# as14120_x31_fpga_power_conf.net
KiCad netlist of a schematic drawn in Altium Designer
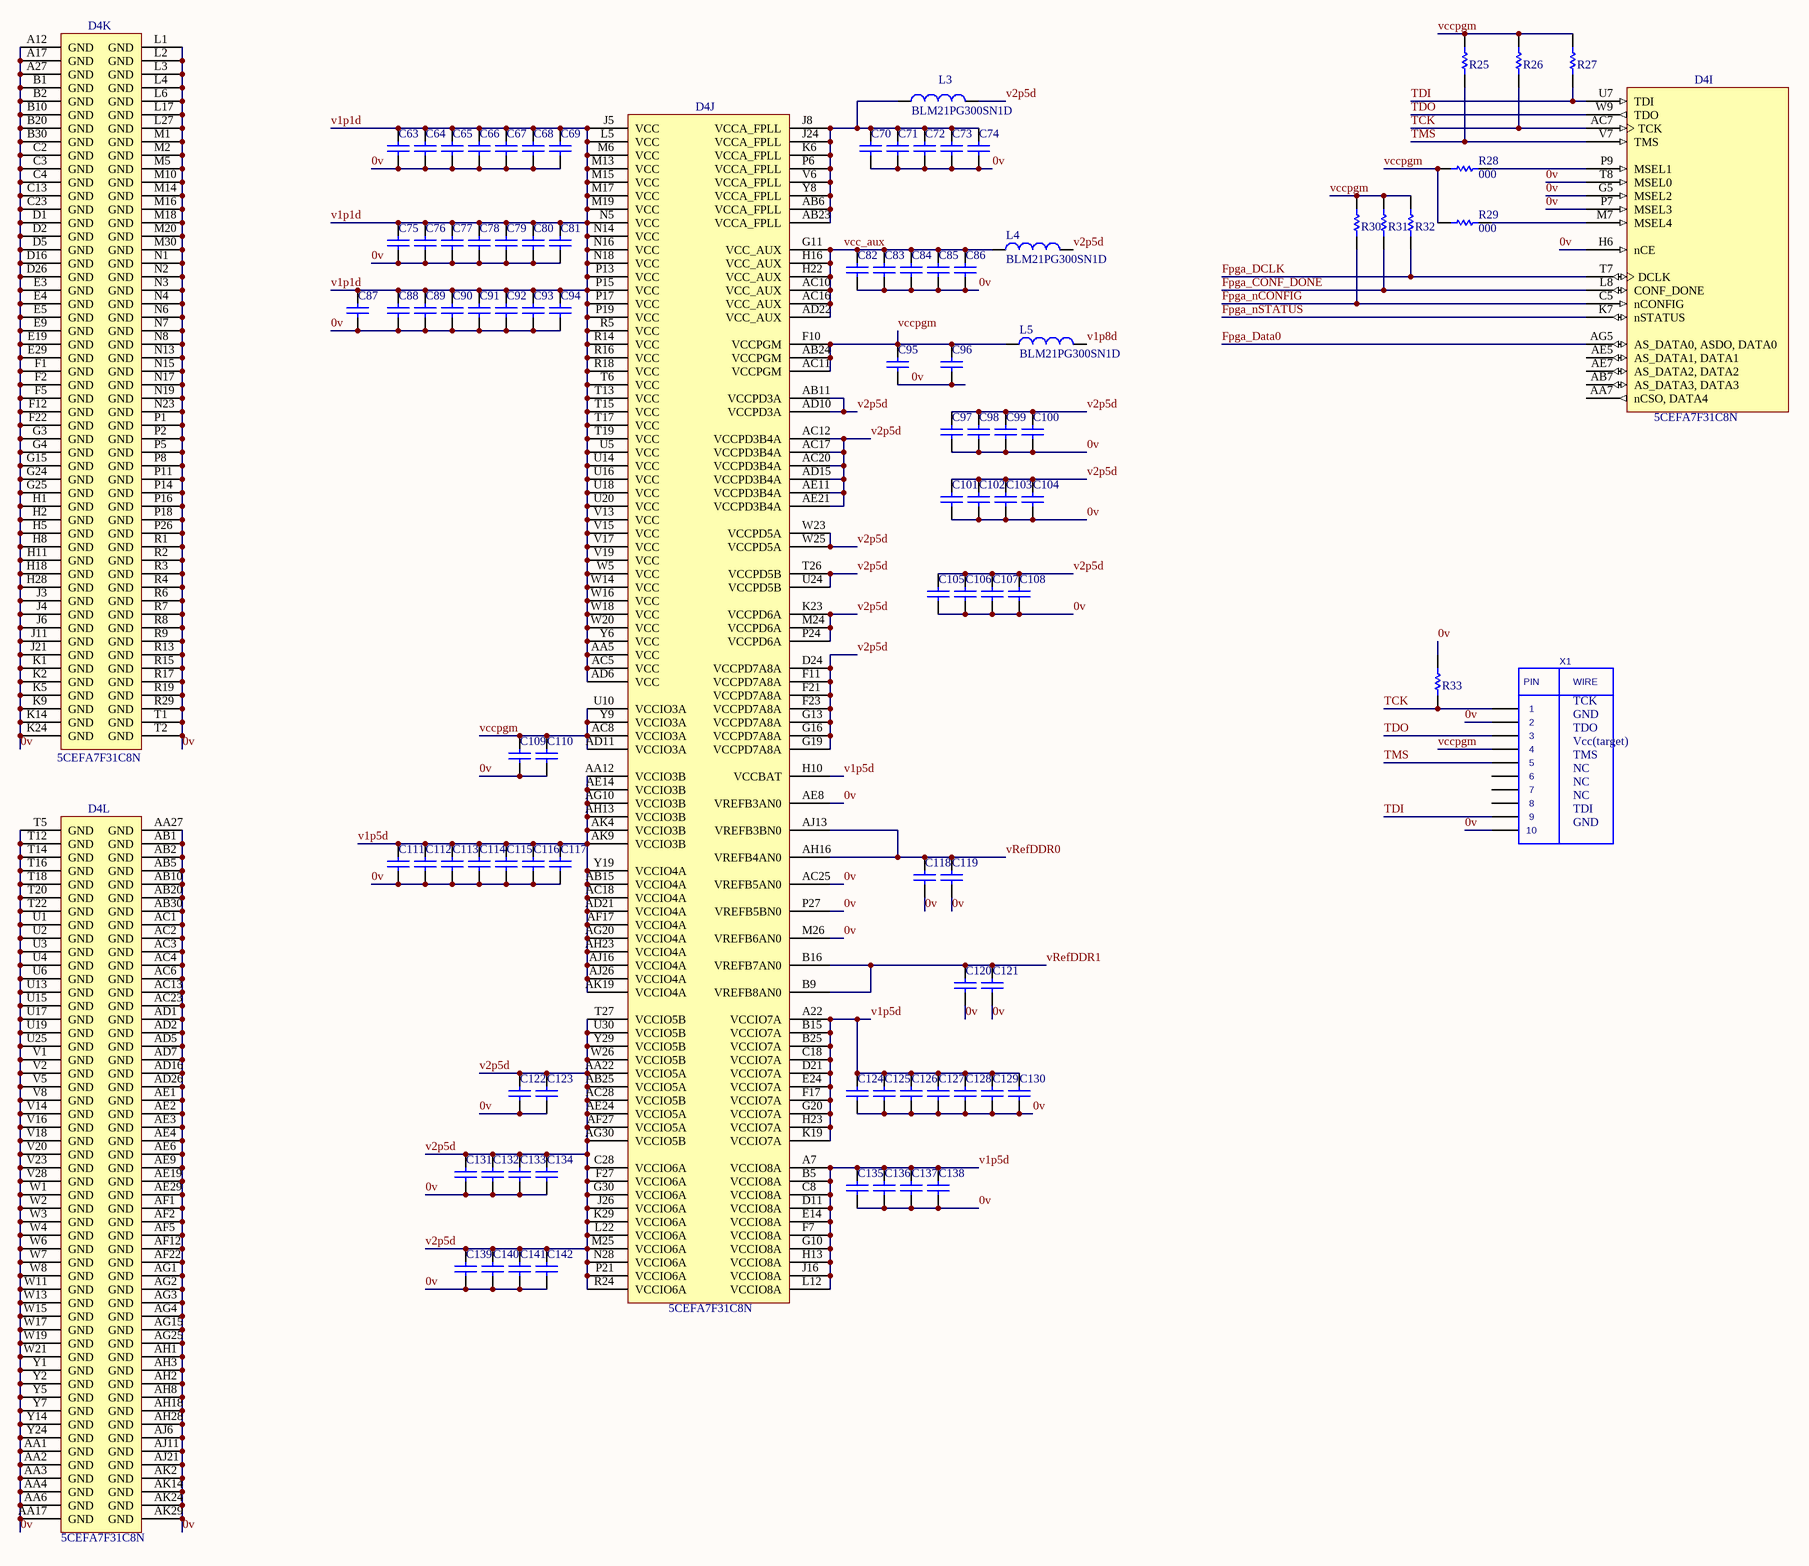
[diagram p0: as14120_x31_fpga_power_conf.SchDoc]

(export (version "E")
  (design (tool "Eeschema 10.0.6"))
  (components
    (comp (ref "C63")
      (value "CAP 1uF 10V 0402(1005)")
      (footprint "CAPC0402(1005)60_M")
      (description "CAP 1uF 10V ±20% 0402 (1005 Metric) Thickness 0.6mm SMD")
      (fields (field (name "TOLERANCE") "±20%"))
      (libsource (lib "as14120") (part "CAP_0402"))
    )
    (comp (ref "C64")
      (value "CAP 1uF 10V 0402(1005)")
      (footprint "CAPC0402(1005)60_M")
      (description "CAP 1uF 10V ±20% 0402 (1005 Metric) Thickness 0.6mm SMD")
      (fields (field (name "TOLERANCE") "±20%"))
      (libsource (lib "as14120") (part "CAP_0402"))
    )
    (comp (ref "C65")
      (value "CAP 1uF 10V 0402(1005)")
      (footprint "CAPC0402(1005)60_M")
      (description "CAP 1uF 10V ±20% 0402 (1005 Metric) Thickness 0.6mm SMD")
      (fields (field (name "TOLERANCE") "±20%"))
      (libsource (lib "as14120") (part "CAP_0402"))
    )
    (comp (ref "C66")
      (value "CAP 1uF 10V 0402(1005)")
      (footprint "CAPC0402(1005)60_M")
      (description "CAP 1uF 10V ±20% 0402 (1005 Metric) Thickness 0.6mm SMD")
      (fields (field (name "TOLERANCE") "±20%"))
      (libsource (lib "as14120") (part "CAP_0402"))
    )
    (comp (ref "C67")
      (value "CAP 1uF 10V 0402(1005)")
      (footprint "CAPC0402(1005)60_M")
      (description "CAP 1uF 10V ±20% 0402 (1005 Metric) Thickness 0.6mm SMD")
      (fields (field (name "TOLERANCE") "±20%"))
      (libsource (lib "as14120") (part "CAP_0402"))
    )
    (comp (ref "C68")
      (value "CAP 1uF 10V 0402(1005)")
      (footprint "CAPC0402(1005)60_M")
      (description "CAP 1uF 10V ±20% 0402 (1005 Metric) Thickness 0.6mm SMD")
      (fields (field (name "TOLERANCE") "±20%"))
      (libsource (lib "as14120") (part "CAP_0402"))
    )
    (comp (ref "C69")
      (value "CAP 1uF 10V 0402(1005)")
      (footprint "CAPC0402(1005)60_M")
      (description "CAP 1uF 10V ±20% 0402 (1005 Metric) Thickness 0.6mm SMD")
      (fields (field (name "TOLERANCE") "±20%"))
      (libsource (lib "as14120") (part "CAP_0402"))
    )
    (comp (ref "C70")
      (value "CAP 1uF 10V 0402(1005)")
      (footprint "CAPC0402(1005)60_M")
      (description "CAP 1uF 10V ±20% 0402 (1005 Metric) Thickness 0.6mm SMD")
      (fields (field (name "TOLERANCE") "±20%"))
      (libsource (lib "as14120") (part "CAP_0402"))
    )
    (comp (ref "C71")
      (value "CAP 1uF 10V 0402(1005)")
      (footprint "CAPC0402(1005)60_M")
      (description "CAP 1uF 10V ±20% 0402 (1005 Metric) Thickness 0.6mm SMD")
      (fields (field (name "TOLERANCE") "±20%"))
      (libsource (lib "as14120") (part "CAP_0402"))
    )
    (comp (ref "C72")
      (value "CAP 1uF 10V 0402(1005)")
      (footprint "CAPC0402(1005)60_M")
      (description "CAP 1uF 10V ±20% 0402 (1005 Metric) Thickness 0.6mm SMD")
      (fields (field (name "TOLERANCE") "±20%"))
      (libsource (lib "as14120") (part "CAP_0402"))
    )
    (comp (ref "C73")
      (value "CAP 1uF 10V 0402(1005)")
      (footprint "CAPC0402(1005)60_M")
      (description "CAP 1uF 10V ±20% 0402 (1005 Metric) Thickness 0.6mm SMD")
      (fields (field (name "TOLERANCE") "±20%"))
      (libsource (lib "as14120") (part "CAP_0402"))
    )
    (comp (ref "C74")
      (value "CAP 1uF 10V 0402(1005)")
      (footprint "CAPC0402(1005)60_M")
      (description "CAP 1uF 10V ±20% 0402 (1005 Metric) Thickness 0.6mm SMD")
      (fields (field (name "TOLERANCE") "±20%"))
      (libsource (lib "as14120") (part "CAP_0402"))
    )
    (comp (ref "C75")
      (value "CAP 1uF 10V 0402(1005)")
      (footprint "CAPC0402(1005)60_M")
      (description "CAP 1uF 10V ±20% 0402 (1005 Metric) Thickness 0.6mm SMD")
      (fields (field (name "TOLERANCE") "±20%"))
      (libsource (lib "as14120") (part "CAP_0402"))
    )
    (comp (ref "C76")
      (value "CAP 1uF 10V 0402(1005)")
      (footprint "CAPC0402(1005)60_M")
      (description "CAP 1uF 10V ±20% 0402 (1005 Metric) Thickness 0.6mm SMD")
      (fields (field (name "TOLERANCE") "±20%"))
      (libsource (lib "as14120") (part "CAP_0402"))
    )
    (comp (ref "C77")
      (value "CAP 1uF 10V 0402(1005)")
      (footprint "CAPC0402(1005)60_M")
      (description "CAP 1uF 10V ±20% 0402 (1005 Metric) Thickness 0.6mm SMD")
      (fields (field (name "TOLERANCE") "±20%"))
      (libsource (lib "as14120") (part "CAP_0402"))
    )
    (comp (ref "C78")
      (value "CAP 1uF 10V 0402(1005)")
      (footprint "CAPC0402(1005)60_M")
      (description "CAP 1uF 10V ±20% 0402 (1005 Metric) Thickness 0.6mm SMD")
      (fields (field (name "TOLERANCE") "±20%"))
      (libsource (lib "as14120") (part "CAP_0402"))
    )
    (comp (ref "C79")
      (value "CAP 1uF 10V 0402(1005)")
      (footprint "CAPC0402(1005)60_M")
      (description "CAP 1uF 10V ±20% 0402 (1005 Metric) Thickness 0.6mm SMD")
      (fields (field (name "TOLERANCE") "±20%"))
      (libsource (lib "as14120") (part "CAP_0402"))
    )
    (comp (ref "C80")
      (value "CAP 1uF 10V 0402(1005)")
      (footprint "CAPC0402(1005)60_M")
      (description "CAP 1uF 10V ±20% 0402 (1005 Metric) Thickness 0.6mm SMD")
      (fields (field (name "TOLERANCE") "±20%"))
      (libsource (lib "as14120") (part "CAP_0402"))
    )
    (comp (ref "C81")
      (value "CAP 1uF 10V 0402(1005)")
      (footprint "CAPC0402(1005)60_M")
      (description "CAP 1uF 10V ±20% 0402 (1005 Metric) Thickness 0.6mm SMD")
      (fields (field (name "TOLERANCE") "±20%"))
      (libsource (lib "as14120") (part "CAP_0402"))
    )
    (comp (ref "C82")
      (value "CAP 1uF 10V 0402(1005)")
      (footprint "CAPC0402(1005)60_M")
      (description "CAP 1uF 10V ±20% 0402 (1005 Metric) Thickness 0.6mm SMD")
      (fields (field (name "TOLERANCE") "±20%"))
      (libsource (lib "as14120") (part "CAP_0402"))
    )
    (comp (ref "C83")
      (value "CAP 1uF 10V 0402(1005)")
      (footprint "CAPC0402(1005)60_M")
      (description "CAP 1uF 10V ±20% 0402 (1005 Metric) Thickness 0.6mm SMD")
      (fields (field (name "TOLERANCE") "±20%"))
      (libsource (lib "as14120") (part "CAP_0402"))
    )
    (comp (ref "C84")
      (value "CAP 1uF 10V 0402(1005)")
      (footprint "CAPC0402(1005)60_M")
      (description "CAP 1uF 10V ±20% 0402 (1005 Metric) Thickness 0.6mm SMD")
      (fields (field (name "TOLERANCE") "±20%"))
      (libsource (lib "as14120") (part "CAP_0402"))
    )
    (comp (ref "C85")
      (value "CAP 1uF 10V 0402(1005)")
      (footprint "CAPC0402(1005)60_M")
      (description "CAP 1uF 10V ±20% 0402 (1005 Metric) Thickness 0.6mm SMD")
      (fields (field (name "TOLERANCE") "±20%"))
      (libsource (lib "as14120") (part "CAP_0402"))
    )
    (comp (ref "C86")
      (value "CAP 1uF 10V 0402(1005)")
      (footprint "CAPC0402(1005)60_M")
      (description "CAP 1uF 10V ±20% 0402 (1005 Metric) Thickness 0.6mm SMD")
      (fields (field (name "TOLERANCE") "±20%"))
      (libsource (lib "as14120") (part "CAP_0402"))
    )
    (comp (ref "C87")
      (value "CAP 1uF 10V 0402(1005)")
      (footprint "CAPC0402(1005)60_M")
      (description "CAP 1uF 10V ±20% 0402 (1005 Metric) Thickness 0.6mm SMD")
      (fields (field (name "TOLERANCE") "±20%"))
      (libsource (lib "as14120") (part "CAP_0402"))
    )
    (comp (ref "C88")
      (value "CAP 1uF 10V 0402(1005)")
      (footprint "CAPC0402(1005)60_M")
      (description "CAP 1uF 10V ±20% 0402 (1005 Metric) Thickness 0.6mm SMD")
      (fields (field (name "TOLERANCE") "±20%"))
      (libsource (lib "as14120") (part "CAP_0402"))
    )
    (comp (ref "C89")
      (value "CAP 1uF 10V 0402(1005)")
      (footprint "CAPC0402(1005)60_M")
      (description "CAP 1uF 10V ±20% 0402 (1005 Metric) Thickness 0.6mm SMD")
      (fields (field (name "TOLERANCE") "±20%"))
      (libsource (lib "as14120") (part "CAP_0402"))
    )
    (comp (ref "C90")
      (value "CAP 1uF 10V 0402(1005)")
      (footprint "CAPC0402(1005)60_M")
      (description "CAP 1uF 10V ±20% 0402 (1005 Metric) Thickness 0.6mm SMD")
      (fields (field (name "TOLERANCE") "±20%"))
      (libsource (lib "as14120") (part "CAP_0402"))
    )
    (comp (ref "C91")
      (value "CAP 1uF 10V 0402(1005)")
      (footprint "CAPC0402(1005)60_M")
      (description "CAP 1uF 10V ±20% 0402 (1005 Metric) Thickness 0.6mm SMD")
      (fields (field (name "TOLERANCE") "±20%"))
      (libsource (lib "as14120") (part "CAP_0402"))
    )
    (comp (ref "C92")
      (value "CAP 1uF 10V 0402(1005)")
      (footprint "CAPC0402(1005)60_M")
      (description "CAP 1uF 10V ±20% 0402 (1005 Metric) Thickness 0.6mm SMD")
      (fields (field (name "TOLERANCE") "±20%"))
      (libsource (lib "as14120") (part "CAP_0402"))
    )
    (comp (ref "C93")
      (value "CAP 1uF 10V 0402(1005)")
      (footprint "CAPC0402(1005)60_M")
      (description "CAP 1uF 10V ±20% 0402 (1005 Metric) Thickness 0.6mm SMD")
      (fields (field (name "TOLERANCE") "±20%"))
      (libsource (lib "as14120") (part "CAP_0402"))
    )
    (comp (ref "C94")
      (value "CAP 1uF 10V 0402(1005)")
      (footprint "CAPC0402(1005)60_M")
      (description "CAP 1uF 10V ±20% 0402 (1005 Metric) Thickness 0.6mm SMD")
      (fields (field (name "TOLERANCE") "±20%"))
      (libsource (lib "as14120") (part "CAP_0402"))
    )
    (comp (ref "C95")
      (value "CAP 1uF 10V 0402(1005)")
      (footprint "CAPC0402(1005)60_M")
      (description "CAP 1uF 10V ±20% 0402 (1005 Metric) Thickness 0.6mm SMD")
      (fields (field (name "TOLERANCE") "±20%"))
      (libsource (lib "as14120") (part "CAP_0402"))
    )
    (comp (ref "C96")
      (value "CAP 1uF 10V 0402(1005)")
      (footprint "CAPC0402(1005)60_M")
      (description "CAP 1uF 10V ±20% 0402 (1005 Metric) Thickness 0.6mm SMD")
      (fields (field (name "TOLERANCE") "±20%"))
      (libsource (lib "as14120") (part "CAP_0402"))
    )
    (comp (ref "C97")
      (value "CAP 1uF 10V 0402(1005)")
      (footprint "CAPC0402(1005)60_M")
      (description "CAP 1uF 10V ±20% 0402 (1005 Metric) Thickness 0.6mm SMD")
      (fields (field (name "TOLERANCE") "±20%"))
      (libsource (lib "as14120") (part "CAP_0402"))
    )
    (comp (ref "C98")
      (value "CAP 1uF 10V 0402(1005)")
      (footprint "CAPC0402(1005)60_M")
      (description "CAP 1uF 10V ±20% 0402 (1005 Metric) Thickness 0.6mm SMD")
      (fields (field (name "TOLERANCE") "±20%"))
      (libsource (lib "as14120") (part "CAP_0402"))
    )
    (comp (ref "C99")
      (value "CAP 1uF 10V 0402(1005)")
      (footprint "CAPC0402(1005)60_M")
      (description "CAP 1uF 10V ±20% 0402 (1005 Metric) Thickness 0.6mm SMD")
      (fields (field (name "TOLERANCE") "±20%"))
      (libsource (lib "as14120") (part "CAP_0402"))
    )
    (comp (ref "C100")
      (value "CAP 1uF 10V 0402(1005)")
      (footprint "CAPC0402(1005)60_M")
      (description "CAP 1uF 10V ±20% 0402 (1005 Metric) Thickness 0.6mm SMD")
      (fields (field (name "TOLERANCE") "±20%"))
      (libsource (lib "as14120") (part "CAP_0402"))
    )
    (comp (ref "C101")
      (value "CAP 1uF 10V 0402(1005)")
      (footprint "CAPC0402(1005)60_M")
      (description "CAP 1uF 10V ±20% 0402 (1005 Metric) Thickness 0.6mm SMD")
      (fields (field (name "TOLERANCE") "±20%"))
      (libsource (lib "as14120") (part "CAP_0402"))
    )
    (comp (ref "C102")
      (value "CAP 1uF 10V 0402(1005)")
      (footprint "CAPC0402(1005)60_M")
      (description "CAP 1uF 10V ±20% 0402 (1005 Metric) Thickness 0.6mm SMD")
      (fields (field (name "TOLERANCE") "±20%"))
      (libsource (lib "as14120") (part "CAP_0402"))
    )
    (comp (ref "C103")
      (value "CAP 1uF 10V 0402(1005)")
      (footprint "CAPC0402(1005)60_M")
      (description "CAP 1uF 10V ±20% 0402 (1005 Metric) Thickness 0.6mm SMD")
      (fields (field (name "TOLERANCE") "±20%"))
      (libsource (lib "as14120") (part "CAP_0402"))
    )
    (comp (ref "C104")
      (value "CAP 1uF 10V 0402(1005)")
      (footprint "CAPC0402(1005)60_M")
      (description "CAP 1uF 10V ±20% 0402 (1005 Metric) Thickness 0.6mm SMD")
      (fields (field (name "TOLERANCE") "±20%"))
      (libsource (lib "as14120") (part "CAP_0402"))
    )
    (comp (ref "C105")
      (value "CAP 1uF 10V 0402(1005)")
      (footprint "CAPC0402(1005)60_M")
      (description "CAP 1uF 10V ±20% 0402 (1005 Metric) Thickness 0.6mm SMD")
      (fields (field (name "TOLERANCE") "±20%"))
      (libsource (lib "as14120") (part "CAP_0402"))
    )
    (comp (ref "C106")
      (value "CAP 1uF 10V 0402(1005)")
      (footprint "CAPC0402(1005)60_M")
      (description "CAP 1uF 10V ±20% 0402 (1005 Metric) Thickness 0.6mm SMD")
      (fields (field (name "TOLERANCE") "±20%"))
      (libsource (lib "as14120") (part "CAP_0402"))
    )
    (comp (ref "C107")
      (value "CAP 1uF 10V 0402(1005)")
      (footprint "CAPC0402(1005)60_M")
      (description "CAP 1uF 10V ±20% 0402 (1005 Metric) Thickness 0.6mm SMD")
      (fields (field (name "TOLERANCE") "±20%"))
      (libsource (lib "as14120") (part "CAP_0402"))
    )
    (comp (ref "C108")
      (value "CAP 1uF 10V 0402(1005)")
      (footprint "CAPC0402(1005)60_M")
      (description "CAP 1uF 10V ±20% 0402 (1005 Metric) Thickness 0.6mm SMD")
      (fields (field (name "TOLERANCE") "±20%"))
      (libsource (lib "as14120") (part "CAP_0402"))
    )
    (comp (ref "C109")
      (value "CAP 1uF 10V 0402(1005)")
      (footprint "CAPC0402(1005)60_M")
      (description "CAP 1uF 10V ±20% 0402 (1005 Metric) Thickness 0.6mm SMD")
      (fields (field (name "TOLERANCE") "±20%"))
      (libsource (lib "as14120") (part "CAP_0402"))
    )
    (comp (ref "C110")
      (value "CAP 1uF 10V 0402(1005)")
      (footprint "CAPC0402(1005)60_M")
      (description "CAP 1uF 10V ±20% 0402 (1005 Metric) Thickness 0.6mm SMD")
      (fields (field (name "TOLERANCE") "±20%"))
      (libsource (lib "as14120") (part "CAP_0402"))
    )
    (comp (ref "C111")
      (value "CAP 1uF 10V 0402(1005)")
      (footprint "CAPC0402(1005)60_M")
      (description "CAP 1uF 10V ±20% 0402 (1005 Metric) Thickness 0.6mm SMD")
      (fields (field (name "TOLERANCE") "±20%"))
      (libsource (lib "as14120") (part "CAP_0402"))
    )
    (comp (ref "C112")
      (value "CAP 1uF 10V 0402(1005)")
      (footprint "CAPC0402(1005)60_M")
      (description "CAP 1uF 10V ±20% 0402 (1005 Metric) Thickness 0.6mm SMD")
      (fields (field (name "TOLERANCE") "±20%"))
      (libsource (lib "as14120") (part "CAP_0402"))
    )
    (comp (ref "C113")
      (value "CAP 1uF 10V 0402(1005)")
      (footprint "CAPC0402(1005)60_M")
      (description "CAP 1uF 10V ±20% 0402 (1005 Metric) Thickness 0.6mm SMD")
      (fields (field (name "TOLERANCE") "±20%"))
      (libsource (lib "as14120") (part "CAP_0402"))
    )
    (comp (ref "C114")
      (value "CAP 1uF 10V 0402(1005)")
      (footprint "CAPC0402(1005)60_M")
      (description "CAP 1uF 10V ±20% 0402 (1005 Metric) Thickness 0.6mm SMD")
      (fields (field (name "TOLERANCE") "±20%"))
      (libsource (lib "as14120") (part "CAP_0402"))
    )
    (comp (ref "C115")
      (value "CAP 1uF 10V 0402(1005)")
      (footprint "CAPC0402(1005)60_M")
      (description "CAP 1uF 10V ±20% 0402 (1005 Metric) Thickness 0.6mm SMD")
      (fields (field (name "TOLERANCE") "±20%"))
      (libsource (lib "as14120") (part "CAP_0402"))
    )
    (comp (ref "C116")
      (value "CAP 1uF 10V 0402(1005)")
      (footprint "CAPC0402(1005)60_M")
      (description "CAP 1uF 10V ±20% 0402 (1005 Metric) Thickness 0.6mm SMD")
      (fields (field (name "TOLERANCE") "±20%"))
      (libsource (lib "as14120") (part "CAP_0402"))
    )
    (comp (ref "C117")
      (value "CAP 1uF 10V 0402(1005)")
      (footprint "CAPC0402(1005)60_M")
      (description "CAP 1uF 10V ±20% 0402 (1005 Metric) Thickness 0.6mm SMD")
      (fields (field (name "TOLERANCE") "±20%"))
      (libsource (lib "as14120") (part "CAP_0402"))
    )
    (comp (ref "C118")
      (value "CAP 1uF 10V 0402(1005)")
      (footprint "CAPC0402(1005)60_M")
      (description "CAP 1uF 10V ±20% 0402 (1005 Metric) Thickness 0.6mm SMD")
      (fields (field (name "TOLERANCE") "±20%"))
      (libsource (lib "as14120") (part "CAP_0402"))
    )
    (comp (ref "C119")
      (value "CAP 1uF 10V 0402(1005)")
      (footprint "CAPC0402(1005)60_M")
      (description "CAP 1uF 10V ±20% 0402 (1005 Metric) Thickness 0.6mm SMD")
      (fields (field (name "TOLERANCE") "±20%"))
      (libsource (lib "as14120") (part "CAP_0402"))
    )
    (comp (ref "C120")
      (value "CAP 1uF 10V 0402(1005)")
      (footprint "CAPC0402(1005)60_M")
      (description "CAP 1uF 10V ±20% 0402 (1005 Metric) Thickness 0.6mm SMD")
      (fields (field (name "TOLERANCE") "±20%"))
      (libsource (lib "as14120") (part "CAP_0402"))
    )
    (comp (ref "C121")
      (value "CAP 1uF 10V 0402(1005)")
      (footprint "CAPC0402(1005)60_M")
      (description "CAP 1uF 10V ±20% 0402 (1005 Metric) Thickness 0.6mm SMD")
      (fields (field (name "TOLERANCE") "±20%"))
      (libsource (lib "as14120") (part "CAP_0402"))
    )
    (comp (ref "C122")
      (value "CAP 1uF 10V 0402(1005)")
      (footprint "CAPC0402(1005)60_M")
      (description "CAP 1uF 10V ±20% 0402 (1005 Metric) Thickness 0.6mm SMD")
      (fields (field (name "TOLERANCE") "±20%"))
      (libsource (lib "as14120") (part "CAP_0402"))
    )
    (comp (ref "C123")
      (value "CAP 1uF 10V 0402(1005)")
      (footprint "CAPC0402(1005)60_M")
      (description "CAP 1uF 10V ±20% 0402 (1005 Metric) Thickness 0.6mm SMD")
      (fields (field (name "TOLERANCE") "±20%"))
      (libsource (lib "as14120") (part "CAP_0402"))
    )
    (comp (ref "C124")
      (value "CAP 1uF 10V 0402(1005)")
      (footprint "CAPC0402(1005)60_M")
      (description "CAP 1uF 10V ±20% 0402 (1005 Metric) Thickness 0.6mm SMD")
      (fields (field (name "TOLERANCE") "±20%"))
      (libsource (lib "as14120") (part "CAP_0402"))
    )
    (comp (ref "C125")
      (value "CAP 1uF 10V 0402(1005)")
      (footprint "CAPC0402(1005)60_M")
      (description "CAP 1uF 10V ±20% 0402 (1005 Metric) Thickness 0.6mm SMD")
      (fields (field (name "TOLERANCE") "±20%"))
      (libsource (lib "as14120") (part "CAP_0402"))
    )
    (comp (ref "C126")
      (value "CAP 1uF 10V 0402(1005)")
      (footprint "CAPC0402(1005)60_M")
      (description "CAP 1uF 10V ±20% 0402 (1005 Metric) Thickness 0.6mm SMD")
      (fields (field (name "TOLERANCE") "±20%"))
      (libsource (lib "as14120") (part "CAP_0402"))
    )
    (comp (ref "C127")
      (value "CAP 1uF 10V 0402(1005)")
      (footprint "CAPC0402(1005)60_M")
      (description "CAP 1uF 10V ±20% 0402 (1005 Metric) Thickness 0.6mm SMD")
      (fields (field (name "TOLERANCE") "±20%"))
      (libsource (lib "as14120") (part "CAP_0402"))
    )
    (comp (ref "C128")
      (value "CAP 1uF 10V 0402(1005)")
      (footprint "CAPC0402(1005)60_M")
      (description "CAP 1uF 10V ±20% 0402 (1005 Metric) Thickness 0.6mm SMD")
      (fields (field (name "TOLERANCE") "±20%"))
      (libsource (lib "as14120") (part "CAP_0402"))
    )
    (comp (ref "C129")
      (value "CAP 1uF 10V 0402(1005)")
      (footprint "CAPC0402(1005)60_M")
      (description "CAP 1uF 10V ±20% 0402 (1005 Metric) Thickness 0.6mm SMD")
      (fields (field (name "TOLERANCE") "±20%"))
      (libsource (lib "as14120") (part "CAP_0402"))
    )
    (comp (ref "C130")
      (value "CAP 1uF 10V 0402(1005)")
      (footprint "CAPC0402(1005)60_M")
      (description "CAP 1uF 10V ±20% 0402 (1005 Metric) Thickness 0.6mm SMD")
      (fields (field (name "TOLERANCE") "±20%"))
      (libsource (lib "as14120") (part "CAP_0402"))
    )
    (comp (ref "C131")
      (value "CAP 1uF 10V 0402(1005)")
      (footprint "CAPC0402(1005)60_M")
      (description "CAP 1uF 10V ±20% 0402 (1005 Metric) Thickness 0.6mm SMD")
      (fields (field (name "TOLERANCE") "±20%"))
      (libsource (lib "as14120") (part "CAP_0402"))
    )
    (comp (ref "C132")
      (value "CAP 1uF 10V 0402(1005)")
      (footprint "CAPC0402(1005)60_M")
      (description "CAP 1uF 10V ±20% 0402 (1005 Metric) Thickness 0.6mm SMD")
      (fields (field (name "TOLERANCE") "±20%"))
      (libsource (lib "as14120") (part "CAP_0402"))
    )
    (comp (ref "C133")
      (value "CAP 1uF 10V 0402(1005)")
      (footprint "CAPC0402(1005)60_M")
      (description "CAP 1uF 10V ±20% 0402 (1005 Metric) Thickness 0.6mm SMD")
      (fields (field (name "TOLERANCE") "±20%"))
      (libsource (lib "as14120") (part "CAP_0402"))
    )
    (comp (ref "C134")
      (value "CAP 1uF 10V 0402(1005)")
      (footprint "CAPC0402(1005)60_M")
      (description "CAP 1uF 10V ±20% 0402 (1005 Metric) Thickness 0.6mm SMD")
      (fields (field (name "TOLERANCE") "±20%"))
      (libsource (lib "as14120") (part "CAP_0402"))
    )
    (comp (ref "C135")
      (value "CAP 1uF 10V 0402(1005)")
      (footprint "CAPC0402(1005)60_M")
      (description "CAP 1uF 10V ±20% 0402 (1005 Metric) Thickness 0.6mm SMD")
      (fields (field (name "TOLERANCE") "±20%"))
      (libsource (lib "as14120") (part "CAP_0402"))
    )
    (comp (ref "C136")
      (value "CAP 1uF 10V 0402(1005)")
      (footprint "CAPC0402(1005)60_M")
      (description "CAP 1uF 10V ±20% 0402 (1005 Metric) Thickness 0.6mm SMD")
      (fields (field (name "TOLERANCE") "±20%"))
      (libsource (lib "as14120") (part "CAP_0402"))
    )
    (comp (ref "C137")
      (value "CAP 1uF 10V 0402(1005)")
      (footprint "CAPC0402(1005)60_M")
      (description "CAP 1uF 10V ±20% 0402 (1005 Metric) Thickness 0.6mm SMD")
      (fields (field (name "TOLERANCE") "±20%"))
      (libsource (lib "as14120") (part "CAP_0402"))
    )
    (comp (ref "C138")
      (value "CAP 1uF 10V 0402(1005)")
      (footprint "CAPC0402(1005)60_M")
      (description "CAP 1uF 10V ±20% 0402 (1005 Metric) Thickness 0.6mm SMD")
      (fields (field (name "TOLERANCE") "±20%"))
      (libsource (lib "as14120") (part "CAP_0402"))
    )
    (comp (ref "C139")
      (value "CAP 1uF 10V 0402(1005)")
      (footprint "CAPC0402(1005)60_M")
      (description "CAP 1uF 10V ±20% 0402 (1005 Metric) Thickness 0.6mm SMD")
      (fields (field (name "TOLERANCE") "±20%"))
      (libsource (lib "as14120") (part "CAP_0402"))
    )
    (comp (ref "C140")
      (value "CAP 1uF 10V 0402(1005)")
      (footprint "CAPC0402(1005)60_M")
      (description "CAP 1uF 10V ±20% 0402 (1005 Metric) Thickness 0.6mm SMD")
      (fields (field (name "TOLERANCE") "±20%"))
      (libsource (lib "as14120") (part "CAP_0402"))
    )
    (comp (ref "C141")
      (value "CAP 1uF 10V 0402(1005)")
      (footprint "CAPC0402(1005)60_M")
      (description "CAP 1uF 10V ±20% 0402 (1005 Metric) Thickness 0.6mm SMD")
      (fields (field (name "TOLERANCE") "±20%"))
      (libsource (lib "as14120") (part "CAP_0402"))
    )
    (comp (ref "C142")
      (value "CAP 1uF 10V 0402(1005)")
      (footprint "CAPC0402(1005)60_M")
      (description "CAP 1uF 10V ±20% 0402 (1005 Metric) Thickness 0.6mm SMD")
      (fields (field (name "TOLERANCE") "±20%"))
      (libsource (lib "as14120") (part "CAP_0402"))
    )
    (comp (ref "D4")
      (value "5CEFA7F31C8N")
      (footprint "ALTR-896-FBGA-2000A")
      (fields (field (name "MANUFACTURER") "Altera"))
      (libsource (lib "Altera Cyclone V E") (part "5CEFA7F31C8N"))
    )
    (comp (ref "L3")
      (value "BLM21PG300SN1D")
      (footprint "CAPC0805(2012)100_N")
      (libsource (lib "as14120") (part "Ferrite_beat"))
    )
    (comp (ref "L4")
      (value "BLM21PG300SN1D")
      (footprint "CAPC0805(2012)100_N")
      (libsource (lib "as14120") (part "Ferrite_beat"))
    )
    (comp (ref "L5")
      (value "BLM21PG300SN1D")
      (footprint "CAPC0805(2012)100_N")
      (libsource (lib "as14120") (part "Ferrite_beat"))
    )
    (comp (ref "R25")
      (value "1K 5% 0603(1608)")
      (footprint "RESC0603(1608)_L")
      (description "1K 0.1W 5% 0603 (1608 Metric)  SMD")
      (fields (field (name "TOLERANCE") "5 %") (field (name "POWER") "0.1 W"))
      (libsource (lib "as14120") (part "RES_0603"))
    )
    (comp (ref "R26")
      (value "1K 5% 0603(1608)")
      (footprint "RESC0603(1608)_L")
      (description "1K 0.1W 5% 0603 (1608 Metric)  SMD")
      (fields (field (name "TOLERANCE") "5 %") (field (name "POWER") "0.1 W"))
      (libsource (lib "as14120") (part "RES_0603"))
    )
    (comp (ref "R27")
      (value "1K 5% 0603(1608)")
      (footprint "RESC0603(1608)_L")
      (description "1K 0.1W 5% 0603 (1608 Metric)  SMD")
      (fields (field (name "TOLERANCE") "5 %") (field (name "POWER") "0.1 W"))
      (libsource (lib "as14120") (part "RES_0603"))
    )
    (comp (ref "R28")
      (value "000")
      (footprint "RESC0603(1608)_L")
      (description "1K 0.1W 5% 0603 (1608 Metric)  SMD")
      (fields (field (name "TOLERANCE") "5 %") (field (name "POWER") "0.1 W"))
      (libsource (lib "as14120") (part "RES_0603"))
    )
    (comp (ref "R29")
      (value "000")
      (footprint "RESC0603(1608)_L")
      (description "1K 0.1W 5% 0603 (1608 Metric)  SMD")
      (fields (field (name "TOLERANCE") "5 %") (field (name "POWER") "0.1 W"))
      (libsource (lib "as14120") (part "RES_0603"))
    )
    (comp (ref "R30")
      (value "1K 5% 0603(1608)")
      (footprint "RESC0603(1608)_L")
      (description "1K 0.1W 5% 0603 (1608 Metric)  SMD")
      (fields (field (name "TOLERANCE") "5 %") (field (name "POWER") "0.1 W"))
      (libsource (lib "as14120") (part "RES_0603"))
    )
    (comp (ref "R31")
      (value "1K 5% 0603(1608)")
      (footprint "RESC0603(1608)_L")
      (description "1K 0.1W 5% 0603 (1608 Metric)  SMD")
      (fields (field (name "TOLERANCE") "5 %") (field (name "POWER") "0.1 W"))
      (libsource (lib "as14120") (part "RES_0603"))
    )
    (comp (ref "R32")
      (value "1K 5% 0603(1608)")
      (footprint "RESC0603(1608)_L")
      (description "1K 0.1W 5% 0603 (1608 Metric)  SMD")
      (fields (field (name "TOLERANCE") "5 %") (field (name "POWER") "0.1 W"))
      (libsource (lib "as14120") (part "RES_0603"))
    )
    (comp (ref "R33")
      (value "1K 5% 0603(1608)")
      (footprint "RESC0603(1608)_L")
      (description "1K 0.1W 5% 0603 (1608 Metric)  SMD")
      (fields (field (name "TOLERANCE") "5 %") (field (name "POWER") "0.1 W"))
      (libsource (lib "as14120") (part "RES_0603"))
    )
    (comp (ref "X1") (value "IDC10") (footprint "IDC10M") (libsource (lib "alexsb") (part "IDC10")))
  )
  (nets
    (net (code "1") (name "/0v") (class "Default")
      (node (ref "C100") (pin "1") (pinfunction "1_1") (pintype "passive"))
      (node (ref "C101") (pin "1") (pinfunction "1_1") (pintype "passive"))
      (node (ref "C102") (pin "1") (pinfunction "1_1") (pintype "passive"))
      (node (ref "C103") (pin "1") (pinfunction "1_1") (pintype "passive"))
      (node (ref "C104") (pin "1") (pinfunction "1_1") (pintype "passive"))
      (node (ref "C105") (pin "1") (pinfunction "1_1") (pintype "passive"))
      (node (ref "C106") (pin "1") (pinfunction "1_1") (pintype "passive"))
      (node (ref "C107") (pin "1") (pinfunction "1_1") (pintype "passive"))
      (node (ref "C108") (pin "1") (pinfunction "1_1") (pintype "passive"))
      (node (ref "C109") (pin "1") (pinfunction "1_1") (pintype "passive"))
      (node (ref "C110") (pin "1") (pinfunction "1_1") (pintype "passive"))
      (node (ref "C111") (pin "1") (pinfunction "1_1") (pintype "passive"))
      (node (ref "C112") (pin "1") (pinfunction "1_1") (pintype "passive"))
      (node (ref "C113") (pin "1") (pinfunction "1_1") (pintype "passive"))
      (node (ref "C114") (pin "1") (pinfunction "1_1") (pintype "passive"))
      (node (ref "C115") (pin "1") (pinfunction "1_1") (pintype "passive"))
      (node (ref "C116") (pin "1") (pinfunction "1_1") (pintype "passive"))
      (node (ref "C117") (pin "1") (pinfunction "1_1") (pintype "passive"))
      (node (ref "C118") (pin "1") (pinfunction "1_1") (pintype "passive"))
      (node (ref "C119") (pin "1") (pinfunction "1_1") (pintype "passive"))
      (node (ref "C120") (pin "1") (pinfunction "1_1") (pintype "passive"))
      (node (ref "C121") (pin "1") (pinfunction "1_1") (pintype "passive"))
      (node (ref "C122") (pin "1") (pinfunction "1_1") (pintype "passive"))
      (node (ref "C123") (pin "1") (pinfunction "1_1") (pintype "passive"))
      (node (ref "C124") (pin "1") (pinfunction "1_1") (pintype "passive"))
      (node (ref "C125") (pin "1") (pinfunction "1_1") (pintype "passive"))
      (node (ref "C126") (pin "1") (pinfunction "1_1") (pintype "passive"))
      (node (ref "C127") (pin "1") (pinfunction "1_1") (pintype "passive"))
      (node (ref "C128") (pin "1") (pinfunction "1_1") (pintype "passive"))
      (node (ref "C129") (pin "1") (pinfunction "1_1") (pintype "passive"))
      (node (ref "C130") (pin "1") (pinfunction "1_1") (pintype "passive"))
      (node (ref "C131") (pin "1") (pinfunction "1_1") (pintype "passive"))
      (node (ref "C132") (pin "1") (pinfunction "1_1") (pintype "passive"))
      (node (ref "C133") (pin "1") (pinfunction "1_1") (pintype "passive"))
      (node (ref "C134") (pin "1") (pinfunction "1_1") (pintype "passive"))
      (node (ref "C135") (pin "1") (pinfunction "1_1") (pintype "passive"))
      (node (ref "C136") (pin "1") (pinfunction "1_1") (pintype "passive"))
      (node (ref "C137") (pin "1") (pinfunction "1_1") (pintype "passive"))
      (node (ref "C138") (pin "1") (pinfunction "1_1") (pintype "passive"))
      (node (ref "C139") (pin "1") (pinfunction "1_1") (pintype "passive"))
      (node (ref "C140") (pin "1") (pinfunction "1_1") (pintype "passive"))
      (node (ref "C141") (pin "1") (pinfunction "1_1") (pintype "passive"))
      (node (ref "C142") (pin "1") (pinfunction "1_1") (pintype "passive"))
      (node (ref "C63") (pin "1") (pinfunction "1_1") (pintype "passive"))
      (node (ref "C64") (pin "1") (pinfunction "1_1") (pintype "passive"))
      (node (ref "C65") (pin "1") (pinfunction "1_1") (pintype "passive"))
      (node (ref "C66") (pin "1") (pinfunction "1_1") (pintype "passive"))
      (node (ref "C67") (pin "1") (pinfunction "1_1") (pintype "passive"))
      (node (ref "C68") (pin "1") (pinfunction "1_1") (pintype "passive"))
      (node (ref "C69") (pin "1") (pinfunction "1_1") (pintype "passive"))
      (node (ref "C70") (pin "1") (pinfunction "1_1") (pintype "passive"))
      (node (ref "C71") (pin "1") (pinfunction "1_1") (pintype "passive"))
      (node (ref "C72") (pin "1") (pinfunction "1_1") (pintype "passive"))
      (node (ref "C73") (pin "1") (pinfunction "1_1") (pintype "passive"))
      (node (ref "C74") (pin "1") (pinfunction "1_1") (pintype "passive"))
      (node (ref "C75") (pin "1") (pinfunction "1_1") (pintype "passive"))
      (node (ref "C76") (pin "1") (pinfunction "1_1") (pintype "passive"))
      (node (ref "C77") (pin "1") (pinfunction "1_1") (pintype "passive"))
      (node (ref "C78") (pin "1") (pinfunction "1_1") (pintype "passive"))
      (node (ref "C79") (pin "1") (pinfunction "1_1") (pintype "passive"))
      (node (ref "C80") (pin "1") (pinfunction "1_1") (pintype "passive"))
      (node (ref "C81") (pin "1") (pinfunction "1_1") (pintype "passive"))
      (node (ref "C82") (pin "1") (pinfunction "1_1") (pintype "passive"))
      (node (ref "C83") (pin "1") (pinfunction "1_1") (pintype "passive"))
      (node (ref "C84") (pin "1") (pinfunction "1_1") (pintype "passive"))
      (node (ref "C85") (pin "1") (pinfunction "1_1") (pintype "passive"))
      (node (ref "C86") (pin "1") (pinfunction "1_1") (pintype "passive"))
      (node (ref "C87") (pin "1") (pinfunction "1_1") (pintype "passive"))
      (node (ref "C88") (pin "1") (pinfunction "1_1") (pintype "passive"))
      (node (ref "C89") (pin "1") (pinfunction "1_1") (pintype "passive"))
      (node (ref "C90") (pin "1") (pinfunction "1_1") (pintype "passive"))
      (node (ref "C91") (pin "1") (pinfunction "1_1") (pintype "passive"))
      (node (ref "C92") (pin "1") (pinfunction "1_1") (pintype "passive"))
      (node (ref "C93") (pin "1") (pinfunction "1_1") (pintype "passive"))
      (node (ref "C94") (pin "1") (pinfunction "1_1") (pintype "passive"))
      (node (ref "C95") (pin "1") (pinfunction "1_1") (pintype "passive"))
      (node (ref "C96") (pin "1") (pinfunction "1_1") (pintype "passive"))
      (node (ref "C97") (pin "1") (pinfunction "1_1") (pintype "passive"))
      (node (ref "C98") (pin "1") (pinfunction "1_1") (pintype "passive"))
      (node (ref "C99") (pin "1") (pinfunction "1_1") (pintype "passive"))
      (node (ref "D4") (pin "A12") (pinfunction "GND_A12") (pintype "power_in"))
      (node (ref "D4") (pin "A17") (pinfunction "GND_A17") (pintype "power_in"))
      (node (ref "D4") (pin "A27") (pinfunction "GND_A27") (pintype "power_in"))
      (node (ref "D4") (pin "AA1") (pinfunction "GND_AA1") (pintype "power_in"))
      (node (ref "D4") (pin "AA17") (pinfunction "GND_AA17") (pintype "power_in"))
      (node (ref "D4") (pin "AA2") (pinfunction "GND_AA2") (pintype "power_in"))
      (node (ref "D4") (pin "AA27") (pinfunction "GND_AA27") (pintype "power_in"))
      (node (ref "D4") (pin "AA3") (pinfunction "GND_AA3") (pintype "power_in"))
      (node (ref "D4") (pin "AA4") (pinfunction "GND_AA4") (pintype "power_in"))
      (node (ref "D4") (pin "AA6") (pinfunction "GND_AA6") (pintype "power_in"))
      (node (ref "D4") (pin "AB1") (pinfunction "GND_AB1") (pintype "power_in"))
      (node (ref "D4") (pin "AB10") (pinfunction "GND_AB10") (pintype "power_in"))
      (node (ref "D4") (pin "AB2") (pinfunction "GND_AB2") (pintype "power_in"))
      (node (ref "D4") (pin "AB20") (pinfunction "GND_AB20") (pintype "power_in"))
      (node (ref "D4") (pin "AB30") (pinfunction "GND_AB30") (pintype "power_in"))
      (node (ref "D4") (pin "AB5") (pinfunction "GND_AB5") (pintype "power_in"))
      (node (ref "D4") (pin "AC1") (pinfunction "GND_AC1") (pintype "power_in"))
      (node (ref "D4") (pin "AC13") (pinfunction "GND_AC13") (pintype "power_in"))
      (node (ref "D4") (pin "AC2") (pinfunction "GND_AC2") (pintype "power_in"))
      (node (ref "D4") (pin "AC23") (pinfunction "GND_AC23") (pintype "power_in"))
      (node (ref "D4") (pin "AC25") (pinfunction "VREFB5AN0_AC25") (pintype "power_in"))
      (node (ref "D4") (pin "AC3") (pinfunction "GND_AC3") (pintype "power_in"))
      (node (ref "D4") (pin "AC4") (pinfunction "GND_AC4") (pintype "power_in"))
      (node (ref "D4") (pin "AC6") (pinfunction "GND_AC6") (pintype "power_in"))
      (node (ref "D4") (pin "AD1") (pinfunction "GND_AD1") (pintype "power_in"))
      (node (ref "D4") (pin "AD16") (pinfunction "GND_AD16") (pintype "power_in"))
      (node (ref "D4") (pin "AD2") (pinfunction "GND_AD2") (pintype "power_in"))
      (node (ref "D4") (pin "AD26") (pinfunction "GND_AD26") (pintype "power_in"))
      (node (ref "D4") (pin "AD5") (pinfunction "GND_AD5") (pintype "power_in"))
      (node (ref "D4") (pin "AD7") (pinfunction "GND_AD7") (pintype "power_in"))
      (node (ref "D4") (pin "AE1") (pinfunction "GND_AE1") (pintype "power_in"))
      (node (ref "D4") (pin "AE19") (pinfunction "GND_AE19") (pintype "power_in"))
      (node (ref "D4") (pin "AE2") (pinfunction "GND_AE2") (pintype "power_in"))
      (node (ref "D4") (pin "AE29") (pinfunction "GND_AE29") (pintype "power_in"))
      (node (ref "D4") (pin "AE3") (pinfunction "GND_AE3") (pintype "power_in"))
      (node (ref "D4") (pin "AE4") (pinfunction "GND_AE4") (pintype "power_in"))
      (node (ref "D4") (pin "AE6") (pinfunction "GND_AE6") (pintype "power_in"))
      (node (ref "D4") (pin "AE8") (pinfunction "VREFB3AN0_AE8") (pintype "power_in"))
      (node (ref "D4") (pin "AE9") (pinfunction "GND_AE9") (pintype "power_in"))
      (node (ref "D4") (pin "AF1") (pinfunction "GND_AF1") (pintype "power_in"))
      (node (ref "D4") (pin "AF12") (pinfunction "GND_AF12") (pintype "power_in"))
      (node (ref "D4") (pin "AF2") (pinfunction "GND_AF2") (pintype "power_in"))
      (node (ref "D4") (pin "AF22") (pinfunction "GND_AF22") (pintype "power_in"))
      (node (ref "D4") (pin "AF5") (pinfunction "GND_AF5") (pintype "power_in"))
      (node (ref "D4") (pin "AG1") (pinfunction "GND_AG1") (pintype "power_in"))
      (node (ref "D4") (pin "AG15") (pinfunction "GND_AG15") (pintype "power_in"))
      (node (ref "D4") (pin "AG2") (pinfunction "GND_AG2") (pintype "power_in"))
      (node (ref "D4") (pin "AG25") (pinfunction "GND_AG25") (pintype "power_in"))
      (node (ref "D4") (pin "AG3") (pinfunction "GND_AG3") (pintype "power_in"))
      (node (ref "D4") (pin "AG4") (pinfunction "GND_AG4") (pintype "power_in"))
      (node (ref "D4") (pin "AH1") (pinfunction "GND_AH1") (pintype "power_in"))
      (node (ref "D4") (pin "AH18") (pinfunction "GND_AH18") (pintype "power_in"))
      (node (ref "D4") (pin "AH2") (pinfunction "GND_AH2") (pintype "power_in"))
      (node (ref "D4") (pin "AH28") (pinfunction "GND_AH28") (pintype "power_in"))
      (node (ref "D4") (pin "AH3") (pinfunction "GND_AH3") (pintype "power_in"))
      (node (ref "D4") (pin "AH8") (pinfunction "GND_AH8") (pintype "power_in"))
      (node (ref "D4") (pin "AJ11") (pinfunction "GND_AJ11") (pintype "power_in"))
      (node (ref "D4") (pin "AJ21") (pinfunction "GND_AJ21") (pintype "power_in"))
      (node (ref "D4") (pin "AJ6") (pinfunction "GND_AJ6") (pintype "power_in"))
      (node (ref "D4") (pin "AK14") (pinfunction "GND_AK14") (pintype "power_in"))
      (node (ref "D4") (pin "AK2") (pinfunction "GND_AK2") (pintype "power_in"))
      (node (ref "D4") (pin "AK24") (pinfunction "GND_AK24") (pintype "power_in"))
      (node (ref "D4") (pin "AK29") (pinfunction "GND_AK29") (pintype "power_in"))
      (node (ref "D4") (pin "B1") (pinfunction "GND_B1") (pintype "power_in"))
      (node (ref "D4") (pin "B10") (pinfunction "GND_B10") (pintype "power_in"))
      (node (ref "D4") (pin "B2") (pinfunction "GND_B2") (pintype "power_in"))
      (node (ref "D4") (pin "B20") (pinfunction "GND_B20") (pintype "power_in"))
      (node (ref "D4") (pin "B30") (pinfunction "GND_B30") (pintype "power_in"))
      (node (ref "D4") (pin "C13") (pinfunction "GND_C13") (pintype "power_in"))
      (node (ref "D4") (pin "C2") (pinfunction "GND_C2") (pintype "power_in"))
      (node (ref "D4") (pin "C23") (pinfunction "GND_C23") (pintype "power_in"))
      (node (ref "D4") (pin "C3") (pinfunction "GND_C3") (pintype "power_in"))
      (node (ref "D4") (pin "C4") (pinfunction "GND_C4") (pintype "power_in"))
      (node (ref "D4") (pin "D1") (pinfunction "GND_D1") (pintype "power_in"))
      (node (ref "D4") (pin "D16") (pinfunction "GND_D16") (pintype "power_in"))
      (node (ref "D4") (pin "D2") (pinfunction "GND_D2") (pintype "power_in"))
      (node (ref "D4") (pin "D26") (pinfunction "GND_D26") (pintype "power_in"))
      (node (ref "D4") (pin "D5") (pinfunction "GND_D5") (pintype "power_in"))
      (node (ref "D4") (pin "E19") (pinfunction "GND_E19") (pintype "power_in"))
      (node (ref "D4") (pin "E29") (pinfunction "GND_E29") (pintype "power_in"))
      (node (ref "D4") (pin "E3") (pinfunction "GND_E3") (pintype "power_in"))
      (node (ref "D4") (pin "E4") (pinfunction "GND_E4") (pintype "power_in"))
      (node (ref "D4") (pin "E5") (pinfunction "GND_E5") (pintype "power_in"))
      (node (ref "D4") (pin "E9") (pinfunction "GND_E9") (pintype "power_in"))
      (node (ref "D4") (pin "F1") (pinfunction "GND_F1") (pintype "power_in"))
      (node (ref "D4") (pin "F12") (pinfunction "GND_F12") (pintype "power_in"))
      (node (ref "D4") (pin "F2") (pinfunction "GND_F2") (pintype "power_in"))
      (node (ref "D4") (pin "F22") (pinfunction "GND_F22") (pintype "power_in"))
      (node (ref "D4") (pin "F5") (pinfunction "GND_F5") (pintype "power_in"))
      (node (ref "D4") (pin "G15") (pinfunction "GND_G15") (pintype "power_in"))
      (node (ref "D4") (pin "G24") (pinfunction "GND_G24") (pintype "power_in"))
      (node (ref "D4") (pin "G25") (pinfunction "GND_G25") (pintype "power_in"))
      (node (ref "D4") (pin "G3") (pinfunction "GND_G3") (pintype "power_in"))
      (node (ref "D4") (pin "G4") (pinfunction "GND_G4") (pintype "power_in"))
      (node (ref "D4") (pin "G5") (pinfunction "MSEL2_G5") (pintype "input"))
      (node (ref "D4") (pin "H1") (pinfunction "GND_H1") (pintype "power_in"))
      (node (ref "D4") (pin "H11") (pinfunction "GND_H11") (pintype "power_in"))
      (node (ref "D4") (pin "H18") (pinfunction "GND_H18") (pintype "power_in"))
      (node (ref "D4") (pin "H2") (pinfunction "GND_H2") (pintype "power_in"))
      (node (ref "D4") (pin "H28") (pinfunction "GND_H28") (pintype "power_in"))
      (node (ref "D4") (pin "H5") (pinfunction "GND_H5") (pintype "power_in"))
      (node (ref "D4") (pin "H6") (pinfunction "nCE_H6") (pintype "input"))
      (node (ref "D4") (pin "H8") (pinfunction "GND_H8") (pintype "power_in"))
      (node (ref "D4") (pin "J11") (pinfunction "GND_J11") (pintype "power_in"))
      (node (ref "D4") (pin "J21") (pinfunction "GND_J21") (pintype "power_in"))
      (node (ref "D4") (pin "J3") (pinfunction "GND_J3") (pintype "power_in"))
      (node (ref "D4") (pin "J4") (pinfunction "GND_J4") (pintype "power_in"))
      (node (ref "D4") (pin "J6") (pinfunction "GND_J6") (pintype "power_in"))
      (node (ref "D4") (pin "K1") (pinfunction "GND_K1") (pintype "power_in"))
      (node (ref "D4") (pin "K14") (pinfunction "GND_K14") (pintype "power_in"))
      (node (ref "D4") (pin "K2") (pinfunction "GND_K2") (pintype "power_in"))
      (node (ref "D4") (pin "K24") (pinfunction "GND_K24") (pintype "power_in"))
      (node (ref "D4") (pin "K5") (pinfunction "GND_K5") (pintype "power_in"))
      (node (ref "D4") (pin "K9") (pinfunction "GND_K9") (pintype "power_in"))
      (node (ref "D4") (pin "L1") (pinfunction "GND_L1") (pintype "power_in"))
      (node (ref "D4") (pin "L17") (pinfunction "GND_L17") (pintype "power_in"))
      (node (ref "D4") (pin "L2") (pinfunction "GND_L2") (pintype "power_in"))
      (node (ref "D4") (pin "L27") (pinfunction "GND_L27") (pintype "power_in"))
      (node (ref "D4") (pin "L3") (pinfunction "GND_L3") (pintype "power_in"))
      (node (ref "D4") (pin "L4") (pinfunction "GND_L4") (pintype "power_in"))
      (node (ref "D4") (pin "L6") (pinfunction "GND_L6") (pintype "power_in"))
      (node (ref "D4") (pin "M1") (pinfunction "GND_M1") (pintype "power_in"))
      (node (ref "D4") (pin "M10") (pinfunction "GND_M10") (pintype "power_in"))
      (node (ref "D4") (pin "M14") (pinfunction "GND_M14") (pintype "power_in"))
      (node (ref "D4") (pin "M16") (pinfunction "GND_M16") (pintype "power_in"))
      (node (ref "D4") (pin "M18") (pinfunction "GND_M18") (pintype "power_in"))
      (node (ref "D4") (pin "M2") (pinfunction "GND_M2") (pintype "power_in"))
      (node (ref "D4") (pin "M20") (pinfunction "GND_M20") (pintype "power_in"))
      (node (ref "D4") (pin "M26") (pinfunction "VREFB6AN0_M26") (pintype "power_in"))
      (node (ref "D4") (pin "M30") (pinfunction "GND_M30") (pintype "power_in"))
      (node (ref "D4") (pin "M5") (pinfunction "GND_M5") (pintype "power_in"))
      (node (ref "D4") (pin "N1") (pinfunction "GND_N1") (pintype "power_in"))
      (node (ref "D4") (pin "N13") (pinfunction "GND_N13") (pintype "power_in"))
      (node (ref "D4") (pin "N15") (pinfunction "GND_N15") (pintype "power_in"))
      (node (ref "D4") (pin "N17") (pinfunction "GND_N17") (pintype "power_in"))
      (node (ref "D4") (pin "N19") (pinfunction "GND_N19") (pintype "power_in"))
      (node (ref "D4") (pin "N2") (pinfunction "GND_N2") (pintype "power_in"))
      (node (ref "D4") (pin "N23") (pinfunction "GND_N23") (pintype "power_in"))
      (node (ref "D4") (pin "N3") (pinfunction "GND_N3") (pintype "power_in"))
      (node (ref "D4") (pin "N4") (pinfunction "GND_N4") (pintype "power_in"))
      (node (ref "D4") (pin "N6") (pinfunction "GND_N6") (pintype "power_in"))
      (node (ref "D4") (pin "N7") (pinfunction "GND_N7") (pintype "power_in"))
      (node (ref "D4") (pin "N8") (pinfunction "GND_N8") (pintype "power_in"))
      (node (ref "D4") (pin "P1") (pinfunction "GND_P1") (pintype "power_in"))
      (node (ref "D4") (pin "P11") (pinfunction "GND_P11") (pintype "power_in"))
      (node (ref "D4") (pin "P14") (pinfunction "GND_P14") (pintype "power_in"))
      (node (ref "D4") (pin "P16") (pinfunction "GND_P16") (pintype "power_in"))
      (node (ref "D4") (pin "P18") (pinfunction "GND_P18") (pintype "power_in"))
      (node (ref "D4") (pin "P2") (pinfunction "GND_P2") (pintype "power_in"))
      (node (ref "D4") (pin "P26") (pinfunction "GND_P26") (pintype "power_in"))
      (node (ref "D4") (pin "P27") (pinfunction "VREFB5BN0_P27") (pintype "power_in"))
      (node (ref "D4") (pin "P5") (pinfunction "GND_P5") (pintype "power_in"))
      (node (ref "D4") (pin "P7") (pinfunction "MSEL3_P7") (pintype "input"))
      (node (ref "D4") (pin "P8") (pinfunction "GND_P8") (pintype "power_in"))
      (node (ref "D4") (pin "R1") (pinfunction "GND_R1") (pintype "power_in"))
      (node (ref "D4") (pin "R13") (pinfunction "GND_R13") (pintype "power_in"))
      (node (ref "D4") (pin "R15") (pinfunction "GND_R15") (pintype "power_in"))
      (node (ref "D4") (pin "R17") (pinfunction "GND_R17") (pintype "power_in"))
      (node (ref "D4") (pin "R19") (pinfunction "GND_R19") (pintype "power_in"))
      (node (ref "D4") (pin "R2") (pinfunction "GND_R2") (pintype "power_in"))
      (node (ref "D4") (pin "R29") (pinfunction "GND_R29") (pintype "power_in"))
      (node (ref "D4") (pin "R3") (pinfunction "GND_R3") (pintype "power_in"))
      (node (ref "D4") (pin "R4") (pinfunction "GND_R4") (pintype "power_in"))
      (node (ref "D4") (pin "R6") (pinfunction "GND_R6") (pintype "power_in"))
      (node (ref "D4") (pin "R7") (pinfunction "GND_R7") (pintype "power_in"))
      (node (ref "D4") (pin "R8") (pinfunction "GND_R8") (pintype "power_in"))
      (node (ref "D4") (pin "R9") (pinfunction "GND_R9") (pintype "power_in"))
      (node (ref "D4") (pin "T1") (pinfunction "GND_T1") (pintype "power_in"))
      (node (ref "D4") (pin "T12") (pinfunction "GND_T12") (pintype "power_in"))
      (node (ref "D4") (pin "T14") (pinfunction "GND_T14") (pintype "power_in"))
      (node (ref "D4") (pin "T16") (pinfunction "GND_T16") (pintype "power_in"))
      (node (ref "D4") (pin "T18") (pinfunction "GND_T18") (pintype "power_in"))
      (node (ref "D4") (pin "T2") (pinfunction "GND_T2") (pintype "power_in"))
      (node (ref "D4") (pin "T20") (pinfunction "GND_T20") (pintype "power_in"))
      (node (ref "D4") (pin "T22") (pinfunction "GND_T22") (pintype "power_in"))
      (node (ref "D4") (pin "T5") (pinfunction "GND_T5") (pintype "power_in"))
      (node (ref "D4") (pin "T8") (pinfunction "MSEL0_T8") (pintype "input"))
      (node (ref "D4") (pin "U1") (pinfunction "GND_U1") (pintype "power_in"))
      (node (ref "D4") (pin "U13") (pinfunction "GND_U13") (pintype "power_in"))
      (node (ref "D4") (pin "U15") (pinfunction "GND_U15") (pintype "power_in"))
      (node (ref "D4") (pin "U17") (pinfunction "GND_U17") (pintype "power_in"))
      (node (ref "D4") (pin "U19") (pinfunction "GND_U19") (pintype "power_in"))
      (node (ref "D4") (pin "U2") (pinfunction "GND_U2") (pintype "power_in"))
      (node (ref "D4") (pin "U25") (pinfunction "GND_U25") (pintype "power_in"))
      (node (ref "D4") (pin "U3") (pinfunction "GND_U3") (pintype "power_in"))
      (node (ref "D4") (pin "U4") (pinfunction "GND_U4") (pintype "power_in"))
      (node (ref "D4") (pin "U6") (pinfunction "GND_U6") (pintype "power_in"))
      (node (ref "D4") (pin "V1") (pinfunction "GND_V1") (pintype "power_in"))
      (node (ref "D4") (pin "V14") (pinfunction "GND_V14") (pintype "power_in"))
      (node (ref "D4") (pin "V16") (pinfunction "GND_V16") (pintype "power_in"))
      (node (ref "D4") (pin "V18") (pinfunction "GND_V18") (pintype "power_in"))
      (node (ref "D4") (pin "V2") (pinfunction "GND_V2") (pintype "power_in"))
      (node (ref "D4") (pin "V20") (pinfunction "GND_V20") (pintype "power_in"))
      (node (ref "D4") (pin "V23") (pinfunction "GND_V23") (pintype "power_in"))
      (node (ref "D4") (pin "V28") (pinfunction "GND_V28") (pintype "power_in"))
      (node (ref "D4") (pin "V5") (pinfunction "GND_V5") (pintype "power_in"))
      (node (ref "D4") (pin "V8") (pinfunction "GND_V8") (pintype "power_in"))
      (node (ref "D4") (pin "W1") (pinfunction "GND_W1") (pintype "power_in"))
      (node (ref "D4") (pin "W11") (pinfunction "GND_W11") (pintype "power_in"))
      (node (ref "D4") (pin "W13") (pinfunction "GND_W13") (pintype "power_in"))
      (node (ref "D4") (pin "W15") (pinfunction "GND_W15") (pintype "power_in"))
      (node (ref "D4") (pin "W17") (pinfunction "GND_W17") (pintype "power_in"))
      (node (ref "D4") (pin "W19") (pinfunction "GND_W19") (pintype "power_in"))
      (node (ref "D4") (pin "W2") (pinfunction "GND_W2") (pintype "power_in"))
      (node (ref "D4") (pin "W21") (pinfunction "GND_W21") (pintype "power_in"))
      (node (ref "D4") (pin "W3") (pinfunction "GND_W3") (pintype "power_in"))
      (node (ref "D4") (pin "W4") (pinfunction "GND_W4") (pintype "power_in"))
      (node (ref "D4") (pin "W6") (pinfunction "GND_W6") (pintype "power_in"))
      (node (ref "D4") (pin "W7") (pinfunction "GND_W7") (pintype "power_in"))
      (node (ref "D4") (pin "W8") (pinfunction "GND_W8") (pintype "power_in"))
      (node (ref "D4") (pin "Y1") (pinfunction "GND_Y1") (pintype "power_in"))
      (node (ref "D4") (pin "Y14") (pinfunction "GND_Y14") (pintype "power_in"))
      (node (ref "D4") (pin "Y2") (pinfunction "GND_Y2") (pintype "power_in"))
      (node (ref "D4") (pin "Y24") (pinfunction "GND_Y24") (pintype "power_in"))
      (node (ref "D4") (pin "Y5") (pinfunction "GND_Y5") (pintype "power_in"))
      (node (ref "D4") (pin "Y7") (pinfunction "GND_Y7") (pintype "power_in"))
      (node (ref "R33") (pin "1") (pinfunction "1_1") (pintype "passive"))
      (node (ref "X1") (pin "10") (pintype "passive"))
      (node (ref "X1") (pin "2") (pintype "passive"))
    )
    (net (code "2") (name "/Fpga_CONF_DONE") (class "Default")
      (node (ref "D4") (pin "L8") (pinfunction "CONF_DONE_L8") (pintype "bidirectional"))
      (node (ref "R31") (pin "2") (pinfunction "2_2") (pintype "passive"))
    )
    (net (code "3") (name "/Fpga_DCLK") (class "Default")
      (node (ref "D4") (pin "T7") (pinfunction "DCLK_T7") (pintype "bidirectional"))
      (node (ref "R32") (pin "2") (pinfunction "2_2") (pintype "passive"))
    )
    (net (code "4") (name "/Fpga_Data0") (class "Default")
      (node (ref "D4") (pin "AG5") (pinfunction "AS_DATA0,_ASDO,_DATA0_AG5") (pintype "bidirectional"))
    )
    (net (code "5") (name "/Fpga_nCONFIG") (class "Default")
      (node (ref "D4") (pin "C5") (pinfunction "nCONFIG_C5") (pintype "input"))
      (node (ref "R30") (pin "2") (pinfunction "2_2") (pintype "passive"))
    )
    (net (code "6") (name "/Fpga_nSTATUS") (class "Default")
      (node (ref "D4") (pin "K7") (pinfunction "nSTATUS_K7") (pintype "bidirectional"))
    )
    (net (code "7") (name "/TCK") (class "Default")
      (node (ref "D4") (pin "AC7") (pinfunction "TCK_AC7") (pintype "input"))
      (node (ref "R26") (pin "2") (pinfunction "2_2") (pintype "passive"))
      (node (ref "R33") (pin "2") (pinfunction "2_2") (pintype "passive"))
      (node (ref "X1") (pin "1") (pintype "passive"))
    )
    (net (code "8") (name "/TDI") (class "Default")
      (node (ref "D4") (pin "U7") (pinfunction "TDI_U7") (pintype "input"))
      (node (ref "R27") (pin "1") (pinfunction "1_1") (pintype "passive"))
      (node (ref "X1") (pin "9") (pintype "passive"))
    )
    (net (code "9") (name "/TDO") (class "Default")
      (node (ref "D4") (pin "W9") (pinfunction "TDO_W9") (pintype "output"))
      (node (ref "X1") (pin "3") (pintype "passive"))
    )
    (net (code "10") (name "/TMS") (class "Default")
      (node (ref "D4") (pin "V7") (pinfunction "TMS_V7") (pintype "input"))
      (node (ref "R25") (pin "2") (pinfunction "2_2") (pintype "passive"))
      (node (ref "X1") (pin "5") (pintype "passive"))
    )
    (net (code "11") (name "/v1p1d") (class "Default")
      (node (ref "C63") (pin "2") (pinfunction "2_2") (pintype "passive"))
      (node (ref "C64") (pin "2") (pinfunction "2_2") (pintype "passive"))
      (node (ref "C65") (pin "2") (pinfunction "2_2") (pintype "passive"))
      (node (ref "C66") (pin "2") (pinfunction "2_2") (pintype "passive"))
      (node (ref "C67") (pin "2") (pinfunction "2_2") (pintype "passive"))
      (node (ref "C68") (pin "2") (pinfunction "2_2") (pintype "passive"))
      (node (ref "C69") (pin "2") (pinfunction "2_2") (pintype "passive"))
      (node (ref "C75") (pin "2") (pinfunction "2_2") (pintype "passive"))
      (node (ref "C76") (pin "2") (pinfunction "2_2") (pintype "passive"))
      (node (ref "C77") (pin "2") (pinfunction "2_2") (pintype "passive"))
      (node (ref "C78") (pin "2") (pinfunction "2_2") (pintype "passive"))
      (node (ref "C79") (pin "2") (pinfunction "2_2") (pintype "passive"))
      (node (ref "C80") (pin "2") (pinfunction "2_2") (pintype "passive"))
      (node (ref "C81") (pin "2") (pinfunction "2_2") (pintype "passive"))
      (node (ref "C87") (pin "2") (pinfunction "2_2") (pintype "passive"))
      (node (ref "C88") (pin "2") (pinfunction "2_2") (pintype "passive"))
      (node (ref "C89") (pin "2") (pinfunction "2_2") (pintype "passive"))
      (node (ref "C90") (pin "2") (pinfunction "2_2") (pintype "passive"))
      (node (ref "C91") (pin "2") (pinfunction "2_2") (pintype "passive"))
      (node (ref "C92") (pin "2") (pinfunction "2_2") (pintype "passive"))
      (node (ref "C93") (pin "2") (pinfunction "2_2") (pintype "passive"))
      (node (ref "C94") (pin "2") (pinfunction "2_2") (pintype "passive"))
      (node (ref "D4") (pin "AA5") (pinfunction "VCC_AA5") (pintype "power_in"))
      (node (ref "D4") (pin "AC5") (pinfunction "VCC_AC5") (pintype "power_in"))
      (node (ref "D4") (pin "AD6") (pinfunction "VCC_AD6") (pintype "power_in"))
      (node (ref "D4") (pin "J5") (pinfunction "VCC_J5") (pintype "power_in"))
      (node (ref "D4") (pin "L5") (pinfunction "VCC_L5") (pintype "power_in"))
      (node (ref "D4") (pin "M13") (pinfunction "VCC_M13") (pintype "power_in"))
      (node (ref "D4") (pin "M15") (pinfunction "VCC_M15") (pintype "power_in"))
      (node (ref "D4") (pin "M17") (pinfunction "VCC_M17") (pintype "power_in"))
      (node (ref "D4") (pin "M19") (pinfunction "VCC_M19") (pintype "power_in"))
      (node (ref "D4") (pin "M6") (pinfunction "VCC_M6") (pintype "power_in"))
      (node (ref "D4") (pin "N14") (pinfunction "VCC_N14") (pintype "power_in"))
      (node (ref "D4") (pin "N16") (pinfunction "VCC_N16") (pintype "power_in"))
      (node (ref "D4") (pin "N18") (pinfunction "VCC_N18") (pintype "power_in"))
      (node (ref "D4") (pin "N5") (pinfunction "VCC_N5") (pintype "power_in"))
      (node (ref "D4") (pin "P13") (pinfunction "VCC_P13") (pintype "power_in"))
      (node (ref "D4") (pin "P15") (pinfunction "VCC_P15") (pintype "power_in"))
      (node (ref "D4") (pin "P17") (pinfunction "VCC_P17") (pintype "power_in"))
      (node (ref "D4") (pin "P19") (pinfunction "VCC_P19") (pintype "power_in"))
      (node (ref "D4") (pin "R14") (pinfunction "VCC_R14") (pintype "power_in"))
      (node (ref "D4") (pin "R16") (pinfunction "VCC_R16") (pintype "power_in"))
      (node (ref "D4") (pin "R18") (pinfunction "VCC_R18") (pintype "power_in"))
      (node (ref "D4") (pin "R5") (pinfunction "VCC_R5") (pintype "power_in"))
      (node (ref "D4") (pin "T13") (pinfunction "VCC_T13") (pintype "power_in"))
      (node (ref "D4") (pin "T15") (pinfunction "VCC_T15") (pintype "power_in"))
      (node (ref "D4") (pin "T17") (pinfunction "VCC_T17") (pintype "power_in"))
      (node (ref "D4") (pin "T19") (pinfunction "VCC_T19") (pintype "power_in"))
      (node (ref "D4") (pin "T6") (pinfunction "VCC_T6") (pintype "power_in"))
      (node (ref "D4") (pin "U14") (pinfunction "VCC_U14") (pintype "power_in"))
      (node (ref "D4") (pin "U16") (pinfunction "VCC_U16") (pintype "power_in"))
      (node (ref "D4") (pin "U18") (pinfunction "VCC_U18") (pintype "power_in"))
      (node (ref "D4") (pin "U20") (pinfunction "VCC_U20") (pintype "power_in"))
      (node (ref "D4") (pin "U5") (pinfunction "VCC_U5") (pintype "power_in"))
      (node (ref "D4") (pin "V13") (pinfunction "VCC_V13") (pintype "power_in"))
      (node (ref "D4") (pin "V15") (pinfunction "VCC_V15") (pintype "power_in"))
      (node (ref "D4") (pin "V17") (pinfunction "VCC_V17") (pintype "power_in"))
      (node (ref "D4") (pin "V19") (pinfunction "VCC_V19") (pintype "power_in"))
      (node (ref "D4") (pin "W14") (pinfunction "VCC_W14") (pintype "power_in"))
      (node (ref "D4") (pin "W16") (pinfunction "VCC_W16") (pintype "power_in"))
      (node (ref "D4") (pin "W18") (pinfunction "VCC_W18") (pintype "power_in"))
      (node (ref "D4") (pin "W20") (pinfunction "VCC_W20") (pintype "power_in"))
      (node (ref "D4") (pin "W5") (pinfunction "VCC_W5") (pintype "power_in"))
      (node (ref "D4") (pin "Y6") (pinfunction "VCC_Y6") (pintype "power_in"))
    )
    (net (code "12") (name "/v1p5d") (class "Default")
      (node (ref "C111") (pin "2") (pinfunction "2_2") (pintype "passive"))
      (node (ref "C112") (pin "2") (pinfunction "2_2") (pintype "passive"))
      (node (ref "C113") (pin "2") (pinfunction "2_2") (pintype "passive"))
      (node (ref "C114") (pin "2") (pinfunction "2_2") (pintype "passive"))
      (node (ref "C115") (pin "2") (pinfunction "2_2") (pintype "passive"))
      (node (ref "C116") (pin "2") (pinfunction "2_2") (pintype "passive"))
      (node (ref "C117") (pin "2") (pinfunction "2_2") (pintype "passive"))
      (node (ref "C124") (pin "2") (pinfunction "2_2") (pintype "passive"))
      (node (ref "C125") (pin "2") (pinfunction "2_2") (pintype "passive"))
      (node (ref "C126") (pin "2") (pinfunction "2_2") (pintype "passive"))
      (node (ref "C127") (pin "2") (pinfunction "2_2") (pintype "passive"))
      (node (ref "C128") (pin "2") (pinfunction "2_2") (pintype "passive"))
      (node (ref "C129") (pin "2") (pinfunction "2_2") (pintype "passive"))
      (node (ref "C130") (pin "2") (pinfunction "2_2") (pintype "passive"))
      (node (ref "C135") (pin "2") (pinfunction "2_2") (pintype "passive"))
      (node (ref "C136") (pin "2") (pinfunction "2_2") (pintype "passive"))
      (node (ref "C137") (pin "2") (pinfunction "2_2") (pintype "passive"))
      (node (ref "C138") (pin "2") (pinfunction "2_2") (pintype "passive"))
      (node (ref "D4") (pin "A22") (pinfunction "VCCIO7A_A22") (pintype "power_in"))
      (node (ref "D4") (pin "A7") (pinfunction "VCCIO8A_A7") (pintype "power_in"))
      (node (ref "D4") (pin "AA12") (pinfunction "VCCIO3B_AA12") (pintype "power_in"))
      (node (ref "D4") (pin "AB15") (pinfunction "VCCIO4A_AB15") (pintype "power_in"))
      (node (ref "D4") (pin "AC18") (pinfunction "VCCIO4A_AC18") (pintype "power_in"))
      (node (ref "D4") (pin "AD21") (pinfunction "VCCIO4A_AD21") (pintype "power_in"))
      (node (ref "D4") (pin "AE14") (pinfunction "VCCIO3B_AE14") (pintype "power_in"))
      (node (ref "D4") (pin "AF17") (pinfunction "VCCIO4A_AF17") (pintype "power_in"))
      (node (ref "D4") (pin "AG10") (pinfunction "VCCIO3B_AG10") (pintype "power_in"))
      (node (ref "D4") (pin "AG20") (pinfunction "VCCIO4A_AG20") (pintype "power_in"))
      (node (ref "D4") (pin "AH13") (pinfunction "VCCIO3B_AH13") (pintype "power_in"))
      (node (ref "D4") (pin "AH23") (pinfunction "VCCIO4A_AH23") (pintype "power_in"))
      (node (ref "D4") (pin "AJ16") (pinfunction "VCCIO4A_AJ16") (pintype "power_in"))
      (node (ref "D4") (pin "AJ26") (pinfunction "VCCIO4A_AJ26") (pintype "power_in"))
      (node (ref "D4") (pin "AK19") (pinfunction "VCCIO4A_AK19") (pintype "power_in"))
      (node (ref "D4") (pin "AK4") (pinfunction "VCCIO3B_AK4") (pintype "power_in"))
      (node (ref "D4") (pin "AK9") (pinfunction "VCCIO3B_AK9") (pintype "power_in"))
      (node (ref "D4") (pin "B15") (pinfunction "VCCIO7A_B15") (pintype "power_in"))
      (node (ref "D4") (pin "B25") (pinfunction "VCCIO7A_B25") (pintype "power_in"))
      (node (ref "D4") (pin "B5") (pinfunction "VCCIO8A_B5") (pintype "power_in"))
      (node (ref "D4") (pin "C18") (pinfunction "VCCIO7A_C18") (pintype "power_in"))
      (node (ref "D4") (pin "C8") (pinfunction "VCCIO8A_C8") (pintype "power_in"))
      (node (ref "D4") (pin "D11") (pinfunction "VCCIO8A_D11") (pintype "power_in"))
      (node (ref "D4") (pin "D21") (pinfunction "VCCIO7A_D21") (pintype "power_in"))
      (node (ref "D4") (pin "E14") (pinfunction "VCCIO8A_E14") (pintype "power_in"))
      (node (ref "D4") (pin "E24") (pinfunction "VCCIO7A_E24") (pintype "power_in"))
      (node (ref "D4") (pin "F17") (pinfunction "VCCIO7A_F17") (pintype "power_in"))
      (node (ref "D4") (pin "F7") (pinfunction "VCCIO8A_F7") (pintype "power_in"))
      (node (ref "D4") (pin "G10") (pinfunction "VCCIO8A_G10") (pintype "power_in"))
      (node (ref "D4") (pin "G20") (pinfunction "VCCIO7A_G20") (pintype "power_in"))
      (node (ref "D4") (pin "H10") (pinfunction "VCCBAT_H10") (pintype "power_in"))
      (node (ref "D4") (pin "H13") (pinfunction "VCCIO8A_H13") (pintype "power_in"))
      (node (ref "D4") (pin "H23") (pinfunction "VCCIO7A_H23") (pintype "power_in"))
      (node (ref "D4") (pin "J16") (pinfunction "VCCIO8A_J16") (pintype "power_in"))
      (node (ref "D4") (pin "K19") (pinfunction "VCCIO7A_K19") (pintype "power_in"))
      (node (ref "D4") (pin "L12") (pinfunction "VCCIO8A_L12") (pintype "power_in"))
      (node (ref "D4") (pin "Y19") (pinfunction "VCCIO4A_Y19") (pintype "power_in"))
    )
    (net (code "13") (name "/v1p8d") (class "Default")
      (node (ref "L5") (pin "2") (pinfunction "2_2") (pintype "passive"))
    )
    (net (code "14") (name "/v2p5d") (class "Default")
      (node (ref "C100") (pin "2") (pinfunction "2_2") (pintype "passive"))
      (node (ref "C101") (pin "2") (pinfunction "2_2") (pintype "passive"))
      (node (ref "C102") (pin "2") (pinfunction "2_2") (pintype "passive"))
      (node (ref "C103") (pin "2") (pinfunction "2_2") (pintype "passive"))
      (node (ref "C104") (pin "2") (pinfunction "2_2") (pintype "passive"))
      (node (ref "C105") (pin "2") (pinfunction "2_2") (pintype "passive"))
      (node (ref "C106") (pin "2") (pinfunction "2_2") (pintype "passive"))
      (node (ref "C107") (pin "2") (pinfunction "2_2") (pintype "passive"))
      (node (ref "C108") (pin "2") (pinfunction "2_2") (pintype "passive"))
      (node (ref "C122") (pin "2") (pinfunction "2_2") (pintype "passive"))
      (node (ref "C123") (pin "2") (pinfunction "2_2") (pintype "passive"))
      (node (ref "C131") (pin "2") (pinfunction "2_2") (pintype "passive"))
      (node (ref "C132") (pin "2") (pinfunction "2_2") (pintype "passive"))
      (node (ref "C133") (pin "2") (pinfunction "2_2") (pintype "passive"))
      (node (ref "C134") (pin "2") (pinfunction "2_2") (pintype "passive"))
      (node (ref "C139") (pin "2") (pinfunction "2_2") (pintype "passive"))
      (node (ref "C140") (pin "2") (pinfunction "2_2") (pintype "passive"))
      (node (ref "C141") (pin "2") (pinfunction "2_2") (pintype "passive"))
      (node (ref "C142") (pin "2") (pinfunction "2_2") (pintype "passive"))
      (node (ref "C97") (pin "2") (pinfunction "2_2") (pintype "passive"))
      (node (ref "C98") (pin "2") (pinfunction "2_2") (pintype "passive"))
      (node (ref "C99") (pin "2") (pinfunction "2_2") (pintype "passive"))
      (node (ref "D4") (pin "AA22") (pinfunction "VCCIO5A_AA22") (pintype "power_in"))
      (node (ref "D4") (pin "AB11") (pinfunction "VCCPD3A_AB11") (pintype "power_in"))
      (node (ref "D4") (pin "AB25") (pinfunction "VCCIO5A_AB25") (pintype "power_in"))
      (node (ref "D4") (pin "AC12") (pinfunction "VCCPD3B4A_AC12") (pintype "power_in"))
      (node (ref "D4") (pin "AC17") (pinfunction "VCCPD3B4A_AC17") (pintype "power_in"))
      (node (ref "D4") (pin "AC20") (pinfunction "VCCPD3B4A_AC20") (pintype "power_in"))
      (node (ref "D4") (pin "AC28") (pinfunction "VCCIO5B_AC28") (pintype "power_in"))
      (node (ref "D4") (pin "AD10") (pinfunction "VCCPD3A_AD10") (pintype "power_in"))
      (node (ref "D4") (pin "AD15") (pinfunction "VCCPD3B4A_AD15") (pintype "power_in"))
      (node (ref "D4") (pin "AE11") (pinfunction "VCCPD3B4A_AE11") (pintype "power_in"))
      (node (ref "D4") (pin "AE21") (pinfunction "VCCPD3B4A_AE21") (pintype "power_in"))
      (node (ref "D4") (pin "AE24") (pinfunction "VCCIO5A_AE24") (pintype "power_in"))
      (node (ref "D4") (pin "AF27") (pinfunction "VCCIO5A_AF27") (pintype "power_in"))
      (node (ref "D4") (pin "AG30") (pinfunction "VCCIO5B_AG30") (pintype "power_in"))
      (node (ref "D4") (pin "C28") (pinfunction "VCCIO6A_C28") (pintype "power_in"))
      (node (ref "D4") (pin "D24") (pinfunction "VCCPD7A8A_D24") (pintype "power_in"))
      (node (ref "D4") (pin "F11") (pinfunction "VCCPD7A8A_F11") (pintype "power_in"))
      (node (ref "D4") (pin "F21") (pinfunction "VCCPD7A8A_F21") (pintype "power_in"))
      (node (ref "D4") (pin "F23") (pinfunction "VCCPD7A8A_F23") (pintype "power_in"))
      (node (ref "D4") (pin "F27") (pinfunction "VCCIO6A_F27") (pintype "power_in"))
      (node (ref "D4") (pin "G13") (pinfunction "VCCPD7A8A_G13") (pintype "power_in"))
      (node (ref "D4") (pin "G16") (pinfunction "VCCPD7A8A_G16") (pintype "power_in"))
      (node (ref "D4") (pin "G19") (pinfunction "VCCPD7A8A_G19") (pintype "power_in"))
      (node (ref "D4") (pin "G30") (pinfunction "VCCIO6A_G30") (pintype "power_in"))
      (node (ref "D4") (pin "J26") (pinfunction "VCCIO6A_J26") (pintype "power_in"))
      (node (ref "D4") (pin "K23") (pinfunction "VCCPD6A_K23") (pintype "power_in"))
      (node (ref "D4") (pin "K29") (pinfunction "VCCIO6A_K29") (pintype "power_in"))
      (node (ref "D4") (pin "L22") (pinfunction "VCCIO6A_L22") (pintype "power_in"))
      (node (ref "D4") (pin "M24") (pinfunction "VCCPD6A_M24") (pintype "power_in"))
      (node (ref "D4") (pin "M25") (pinfunction "VCCIO6A_M25") (pintype "power_in"))
      (node (ref "D4") (pin "N28") (pinfunction "VCCIO6A_N28") (pintype "power_in"))
      (node (ref "D4") (pin "P21") (pinfunction "VCCIO6A_P21") (pintype "power_in"))
      (node (ref "D4") (pin "P24") (pinfunction "VCCPD6A_P24") (pintype "power_in"))
      (node (ref "D4") (pin "R24") (pinfunction "VCCIO6A_R24") (pintype "power_in"))
      (node (ref "D4") (pin "T26") (pinfunction "VCCPD5B_T26") (pintype "power_in"))
      (node (ref "D4") (pin "T27") (pinfunction "VCCIO5B_T27") (pintype "power_in"))
      (node (ref "D4") (pin "U24") (pinfunction "VCCPD5B_U24") (pintype "power_in"))
      (node (ref "D4") (pin "U30") (pinfunction "VCCIO5B_U30") (pintype "power_in"))
      (node (ref "D4") (pin "W23") (pinfunction "VCCPD5A_W23") (pintype "power_in"))
      (node (ref "D4") (pin "W25") (pinfunction "VCCPD5A_W25") (pintype "power_in"))
      (node (ref "D4") (pin "W26") (pinfunction "VCCIO5B_W26") (pintype "power_in"))
      (node (ref "D4") (pin "Y29") (pinfunction "VCCIO5B_Y29") (pintype "power_in"))
      (node (ref "L3") (pin "2") (pinfunction "2_2") (pintype "passive"))
      (node (ref "L4") (pin "2") (pinfunction "2_2") (pintype "passive"))
    )
    (net (code "15") (name "/vRefDDR0") (class "Default")
      (node (ref "C118") (pin "2") (pinfunction "2_2") (pintype "passive"))
      (node (ref "C119") (pin "2") (pinfunction "2_2") (pintype "passive"))
      (node (ref "D4") (pin "AH16") (pinfunction "VREFB4AN0_AH16") (pintype "power_in"))
      (node (ref "D4") (pin "AJ13") (pinfunction "VREFB3BN0_AJ13") (pintype "power_in"))
    )
    (net (code "16") (name "/vRefDDR1") (class "Default")
      (node (ref "C120") (pin "2") (pinfunction "2_2") (pintype "passive"))
      (node (ref "C121") (pin "2") (pinfunction "2_2") (pintype "passive"))
      (node (ref "D4") (pin "B16") (pinfunction "VREFB7AN0_B16") (pintype "power_in"))
      (node (ref "D4") (pin "B9") (pinfunction "VREFB8AN0_B9") (pintype "power_in"))
    )
    (net (code "17") (name "/vcc_aux") (class "Default")
      (node (ref "C82") (pin "2") (pinfunction "2_2") (pintype "passive"))
      (node (ref "C83") (pin "2") (pinfunction "2_2") (pintype "passive"))
      (node (ref "C84") (pin "2") (pinfunction "2_2") (pintype "passive"))
      (node (ref "C85") (pin "2") (pinfunction "2_2") (pintype "passive"))
      (node (ref "C86") (pin "2") (pinfunction "2_2") (pintype "passive"))
      (node (ref "D4") (pin "AC10") (pinfunction "VCC_AUX_AC10") (pintype "power_in"))
      (node (ref "D4") (pin "AC16") (pinfunction "VCC_AUX_AC16") (pintype "power_in"))
      (node (ref "D4") (pin "AD22") (pinfunction "VCC_AUX_AD22") (pintype "power_in"))
      (node (ref "D4") (pin "G11") (pinfunction "VCC_AUX_G11") (pintype "power_in"))
      (node (ref "D4") (pin "H16") (pinfunction "VCC_AUX_H16") (pintype "power_in"))
      (node (ref "D4") (pin "H22") (pinfunction "VCC_AUX_H22") (pintype "power_in"))
      (node (ref "L4") (pin "1") (pinfunction "1_1") (pintype "passive"))
    )
    (net (code "18") (name "/vccpgm") (class "Default")
      (node (ref "C109") (pin "2") (pinfunction "2_2") (pintype "passive"))
      (node (ref "C110") (pin "2") (pinfunction "2_2") (pintype "passive"))
      (node (ref "C95") (pin "2") (pinfunction "2_2") (pintype "passive"))
      (node (ref "C96") (pin "2") (pinfunction "2_2") (pintype "passive"))
      (node (ref "D4") (pin "AB24") (pinfunction "VCCPGM_AB24") (pintype "power_in"))
      (node (ref "D4") (pin "AC11") (pinfunction "VCCPGM_AC11") (pintype "power_in"))
      (node (ref "D4") (pin "AC8") (pinfunction "VCCIO3A_AC8") (pintype "power_in"))
      (node (ref "D4") (pin "AD11") (pinfunction "VCCIO3A_AD11") (pintype "power_in"))
      (node (ref "D4") (pin "F10") (pinfunction "VCCPGM_F10") (pintype "power_in"))
      (node (ref "D4") (pin "U10") (pinfunction "VCCIO3A_U10") (pintype "power_in"))
      (node (ref "D4") (pin "Y9") (pinfunction "VCCIO3A_Y9") (pintype "power_in"))
      (node (ref "L5") (pin "1") (pinfunction "1_1") (pintype "passive"))
      (node (ref "R25") (pin "1") (pinfunction "1_1") (pintype "passive"))
      (node (ref "R26") (pin "1") (pinfunction "1_1") (pintype "passive"))
      (node (ref "R27") (pin "2") (pinfunction "2_2") (pintype "passive"))
      (node (ref "R28") (pin "2") (pinfunction "2_2") (pintype "passive"))
      (node (ref "R29") (pin "2") (pinfunction "2_2") (pintype "passive"))
      (node (ref "R30") (pin "1") (pinfunction "1_1") (pintype "passive"))
      (node (ref "R31") (pin "1") (pinfunction "1_1") (pintype "passive"))
      (node (ref "R32") (pin "1") (pinfunction "1_1") (pintype "passive"))
      (node (ref "X1") (pin "4") (pintype "passive"))
    )
    (net (code "19") (name "Net-(C70-Pad2)") (class "Default")
      (node (ref "C70") (pin "2") (pinfunction "2_2") (pintype "passive"))
      (node (ref "C71") (pin "2") (pinfunction "2_2") (pintype "passive"))
      (node (ref "C72") (pin "2") (pinfunction "2_2") (pintype "passive"))
      (node (ref "C73") (pin "2") (pinfunction "2_2") (pintype "passive"))
      (node (ref "C74") (pin "2") (pinfunction "2_2") (pintype "passive"))
      (node (ref "D4") (pin "AB23") (pinfunction "VCCA_FPLL_AB23") (pintype "power_in"))
      (node (ref "D4") (pin "AB6") (pinfunction "VCCA_FPLL_AB6") (pintype "power_in"))
      (node (ref "D4") (pin "J24") (pinfunction "VCCA_FPLL_J24") (pintype "power_in"))
      (node (ref "D4") (pin "J8") (pinfunction "VCCA_FPLL_J8") (pintype "power_in"))
      (node (ref "D4") (pin "K6") (pinfunction "VCCA_FPLL_K6") (pintype "power_in"))
      (node (ref "D4") (pin "P6") (pinfunction "VCCA_FPLL_P6") (pintype "power_in"))
      (node (ref "D4") (pin "V6") (pinfunction "VCCA_FPLL_V6") (pintype "power_in"))
      (node (ref "D4") (pin "Y8") (pinfunction "VCCA_FPLL_Y8") (pintype "power_in"))
      (node (ref "L3") (pin "1") (pinfunction "1_1") (pintype "passive"))
    )
    (net (code "20") (name "Net-(D4I-MSEL1)") (class "Default")
      (node (ref "D4") (pin "P9") (pinfunction "MSEL1_P9") (pintype "input"))
      (node (ref "R28") (pin "1") (pinfunction "1_1") (pintype "passive"))
    )
    (net (code "21") (name "Net-(D4I-MSEL4)") (class "Default")
      (node (ref "D4") (pin "M7") (pinfunction "MSEL4_M7") (pintype "input"))
      (node (ref "R29") (pin "1") (pinfunction "1_1") (pintype "passive"))
    )
    (net (code "22") (name "unconnected-(D4I-AS_DATA1,_DATA1-PadAE5)") (class "Default")
      (node (ref "D4") (pin "AE5") (pinfunction "AS_DATA1,_DATA1_AE5") (pintype "bidirectional"))
    )
    (net (code "23") (name "unconnected-(D4I-AS_DATA2,_DATA2-PadAE7)") (class "Default")
      (node (ref "D4") (pin "AE7") (pinfunction "AS_DATA2,_DATA2_AE7") (pintype "bidirectional"))
    )
    (net (code "24") (name "unconnected-(D4I-AS_DATA3,_DATA3-PadAB7)") (class "Default")
      (node (ref "D4") (pin "AB7") (pinfunction "AS_DATA3,_DATA3_AB7") (pintype "bidirectional"))
    )
    (net (code "25") (name "unconnected-(D4I-nCSO,_DATA4-PadAA7)") (class "Default")
      (node (ref "D4") (pin "AA7") (pinfunction "nCSO,_DATA4_AA7") (pintype "output"))
    )
    (net (code "26") (name "unconnected-(X1-Pad6)") (class "Default")
      (node (ref "X1") (pin "6") (pintype "passive"))
    )
    (net (code "27") (name "unconnected-(X1-Pad7)") (class "Default")
      (node (ref "X1") (pin "7") (pintype "passive"))
    )
    (net (code "28") (name "unconnected-(X1-Pad8)") (class "Default")
      (node (ref "X1") (pin "8") (pintype "passive"))
    )
  )
)
